# 11-IMU.net
KiCad netlist of a schematic drawn in Altium Designer
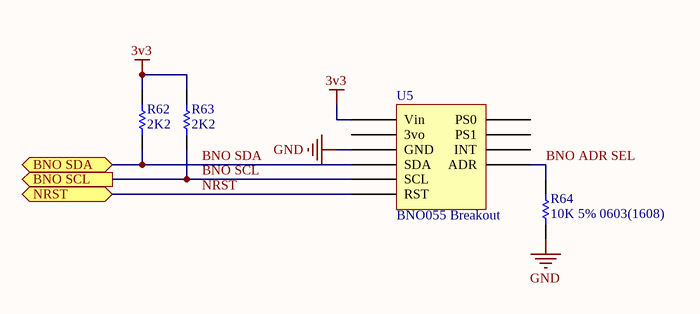
[diagram p0: 11-IMU.SchDoc]

(export (version "E")
  (design (tool "Eeschema 10.0.6"))
  (components
    (comp (ref "R62")
      (value "2K2")
      (footprint "RESC0603(1608)_N")
      (description "2K2 0.1W 5% 0603 (1608 Metric)  SMD")
      (fields (field (name "POWER") "0.1 W") (field (name "TOLERANCE") "5 %"))
      (libsource (lib "Altium Content Vault") (part "RES"))
    )
    (comp (ref "R63")
      (value "2K2")
      (footprint "RESC0603(1608)_N")
      (description "2K2 0.1W 5% 0603 (1608 Metric)  SMD")
      (fields (field (name "POWER") "0.1 W") (field (name "TOLERANCE") "5 %"))
      (libsource (lib "Altium Content Vault") (part "RES"))
    )
    (comp (ref "R64")
      (value "10K 5% 0603(1608)")
      (footprint "RESC0603(1608)_N")
      (description "10K 0.1W 5% 0603 (1608 Metric)  SMD")
      (fields (field (name "TOLERANCE") "5 %") (field (name "POWER") "0.1 W"))
      (libsource (lib "Altium Content Vault") (part "RES"))
    )
    (comp (ref "U5")
      (value "BNO055 Breakout")
      (footprint "BNO055")
      (libsource (lib "VCB20") (part "BNO055 Breakout"))
    )
  )
  (nets
    (net (code "1") (name "/BNO ADR SEL") (class "Default")
      (node (ref "R64") (pin "2") (pinfunction "2_2") (pintype "passive"))
      (node (ref "U5") (pin "10") (pinfunction "ADR_10") (pintype "passive"))
    )
    (net (code "2") (name "/BNO SCL") (class "Default")
      (node (ref "R63") (pin "1") (pinfunction "1_1") (pintype "passive"))
      (node (ref "U5") (pin "5") (pinfunction "SCL_5") (pintype "passive"))
    )
    (net (code "3") (name "/BNO SDA") (class "Default")
      (node (ref "R62") (pin "1") (pinfunction "1_1") (pintype "passive"))
      (node (ref "U5") (pin "4") (pinfunction "SDA_4") (pintype "passive"))
    )
    (net (code "4") (name "/NRST") (class "Default")
      (node (ref "U5") (pin "6") (pinfunction "RST_6") (pintype "passive"))
    )
    (net (code "5") (name "3v3") (class "Default")
      (node (ref "R62") (pin "2") (pinfunction "2_2") (pintype "passive"))
      (node (ref "R63") (pin "2") (pinfunction "2_2") (pintype "passive"))
      (node (ref "U5") (pin "1") (pinfunction "Vin_1") (pintype "passive"))
    )
    (net (code "6") (name "GND") (class "Default")
      (node (ref "R64") (pin "1") (pinfunction "1_1") (pintype "passive"))
      (node (ref "U5") (pin "3") (pinfunction "GND_3") (pintype "passive"))
    )
    (net (code "7") (name "unconnected-(U5-3vo-Pad2)") (class "Default")
      (node (ref "U5") (pin "2") (pinfunction "3vo_2") (pintype "passive"))
    )
    (net (code "8") (name "unconnected-(U5-INT-Pad9)") (class "Default")
      (node (ref "U5") (pin "9") (pinfunction "INT_9") (pintype "passive"))
    )
    (net (code "9") (name "unconnected-(U5-PS0-Pad7)") (class "Default")
      (node (ref "U5") (pin "7") (pinfunction "PS0_7") (pintype "passive"))
    )
    (net (code "10") (name "unconnected-(U5-PS1-Pad8)") (class "Default")
      (node (ref "U5") (pin "8") (pinfunction "PS1_8") (pintype "passive"))
    )
  )
)
